# OPA4377__V1_0.net
KiCad netlist of a schematic drawn in EasyEDA Pro
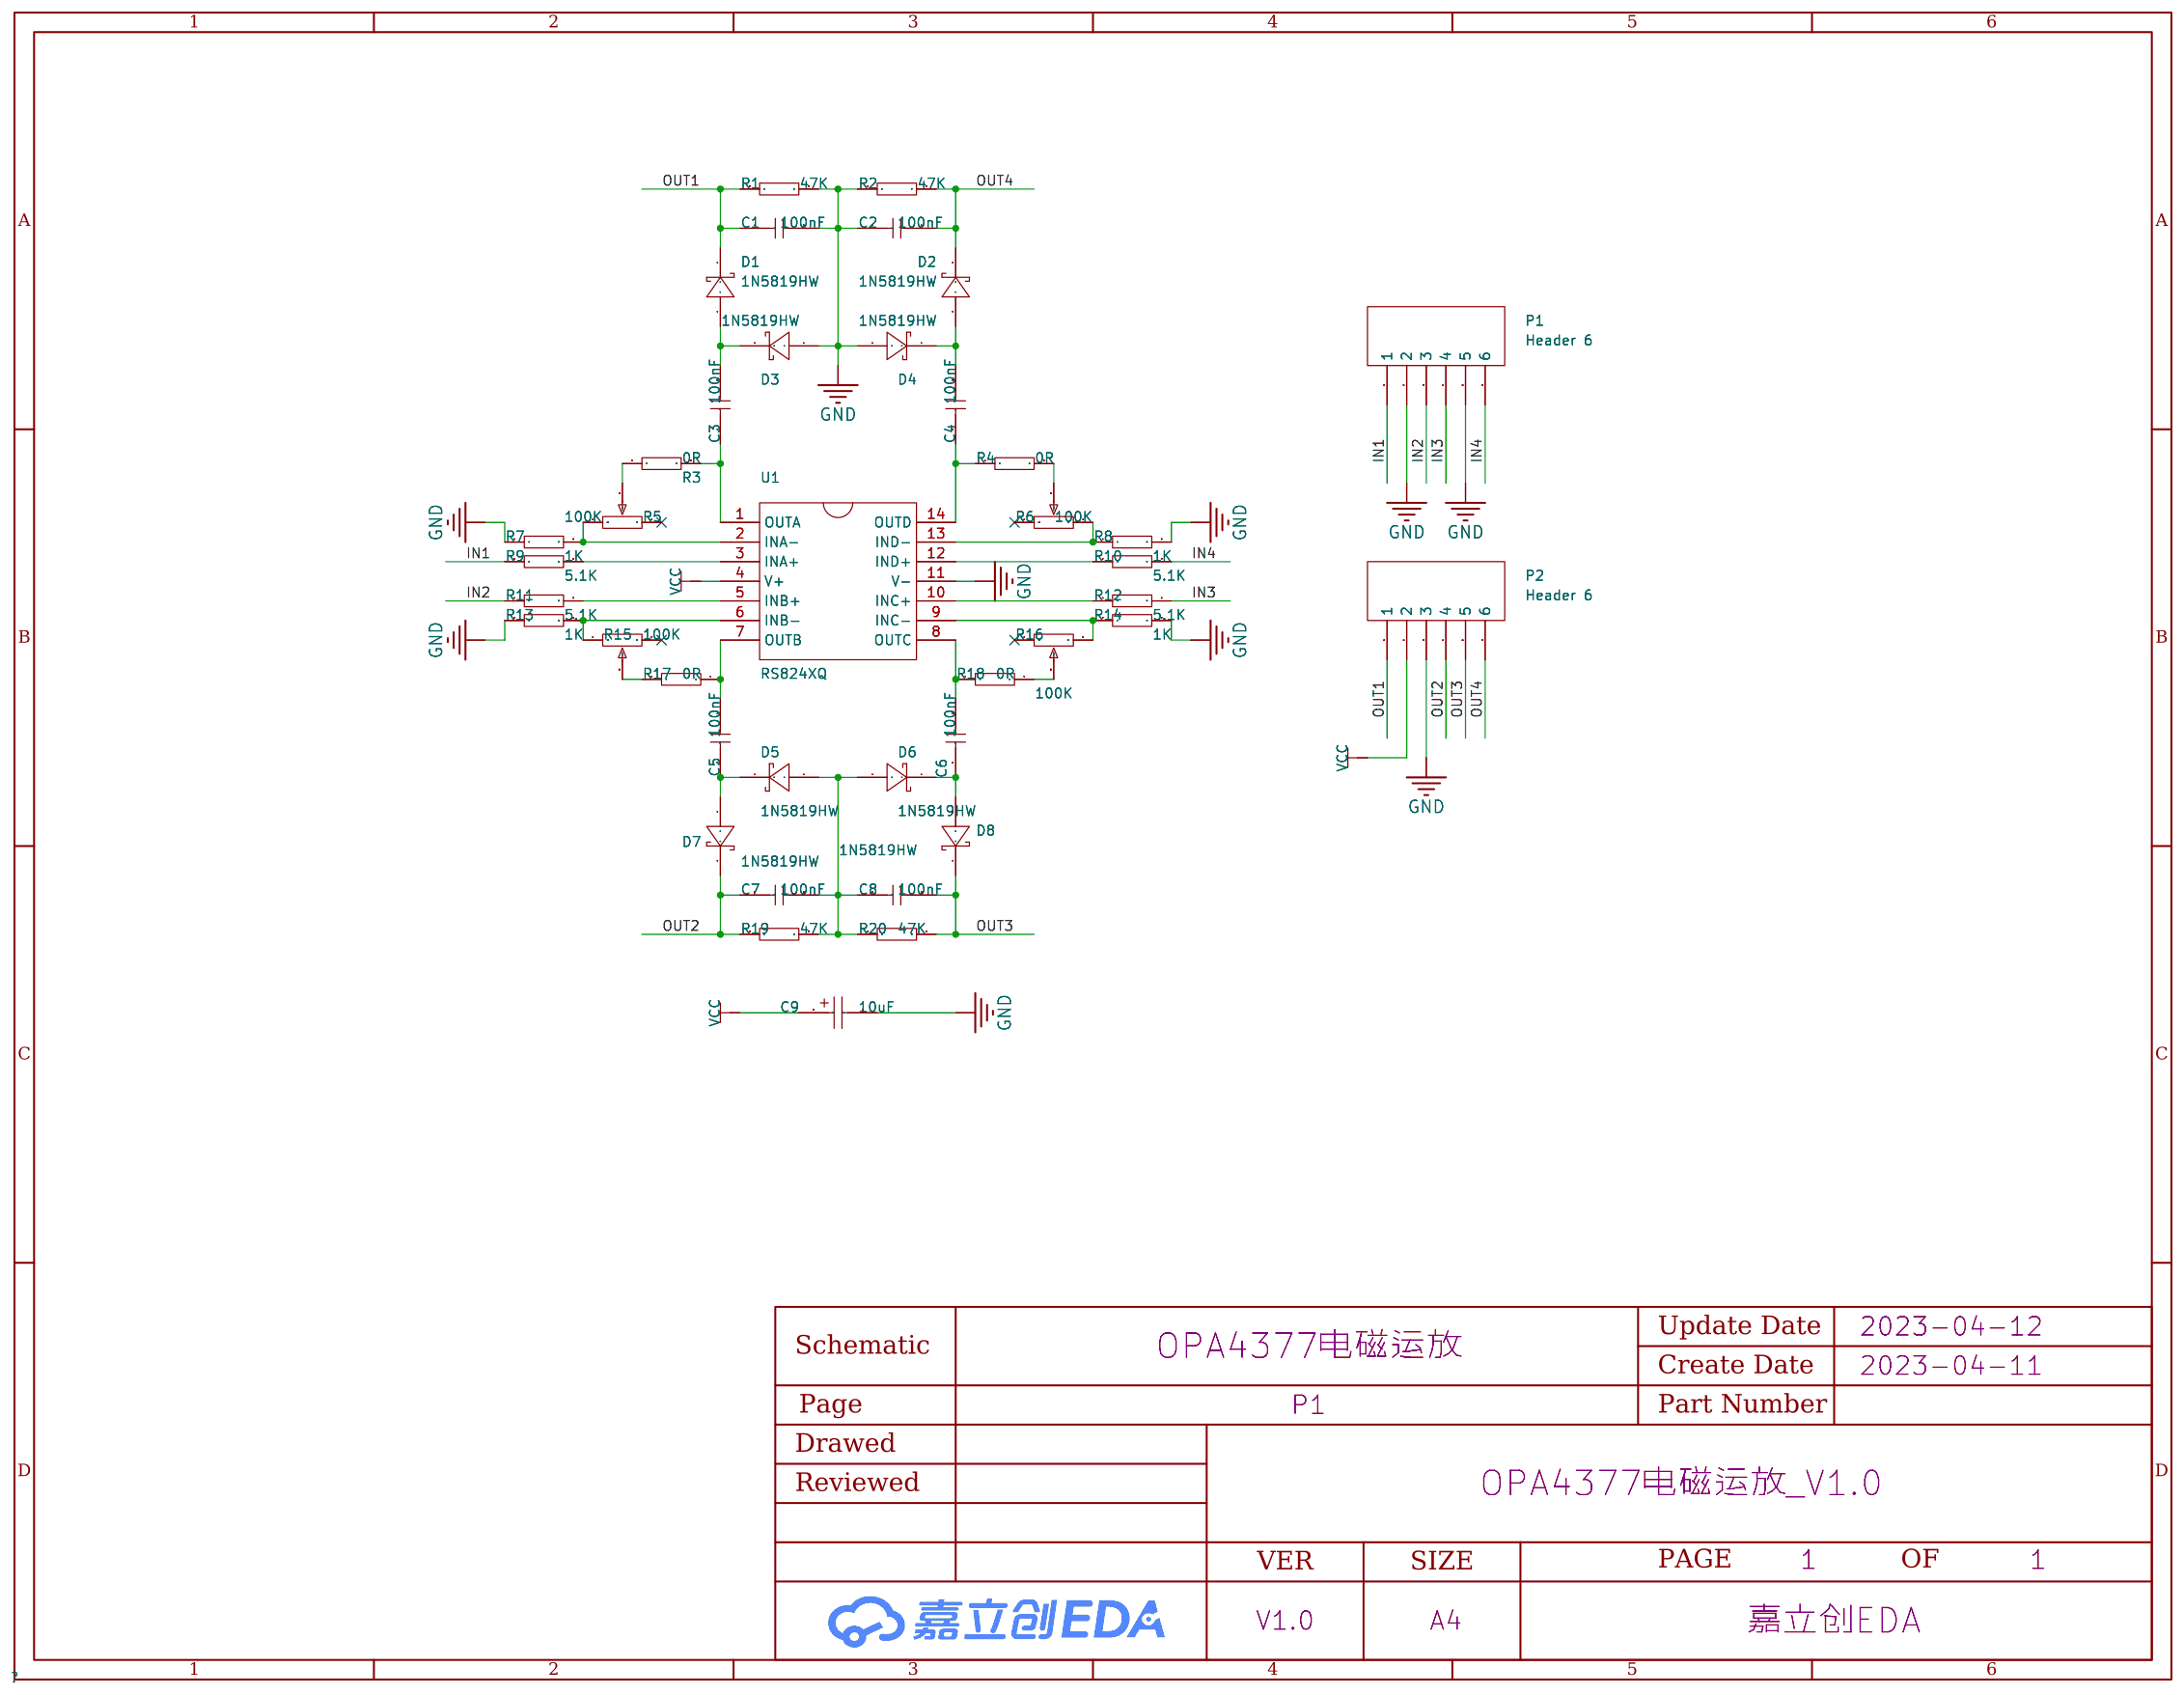
[diagram p0: schematic sheet]

(export (version "E")
  (design (tool "Eeschema 10.0.6"))
  (components
    (comp (ref "C1")
      (value "100nF")
      (footprint "easyedapro:CAPC1608[0603]S-L")
      (libsource (lib "easyedapro") (part "100nF 0603 50V X7R"))
    )
    (comp (ref "C2")
      (value "100nF")
      (footprint "easyedapro:CAPC1608[0603]S-L")
      (libsource (lib "easyedapro") (part "100nF 0603 50V X7R"))
    )
    (comp (ref "C3")
      (value "100nF")
      (footprint "easyedapro:CAPC1608[0603]S-L")
      (libsource (lib "easyedapro") (part "100nF 0603 50V X7R"))
    )
    (comp (ref "C4")
      (value "100nF")
      (footprint "easyedapro:CAPC1608[0603]S-L")
      (libsource (lib "easyedapro") (part "100nF 0603 50V X7R"))
    )
    (comp (ref "C5")
      (value "100nF")
      (footprint "easyedapro:CAPC1608[0603]S-L")
      (libsource (lib "easyedapro") (part "100nF 0603 50V X7R"))
    )
    (comp (ref "C6")
      (value "100nF")
      (footprint "easyedapro:CAPC1608[0603]S-L")
      (libsource (lib "easyedapro") (part "100nF 0603 50V X7R"))
    )
    (comp (ref "C7")
      (value "100nF")
      (footprint "easyedapro:CAPC1608[0603]S-L")
      (libsource (lib "easyedapro") (part "100nF 0603 50V X7R"))
    )
    (comp (ref "C8")
      (value "100nF")
      (footprint "easyedapro:CAPC1608[0603]S-L")
      (libsource (lib "easyedapro") (part "100nF 0603 50V X7R"))
    )
    (comp (ref "C9")
      (value "10uF")
      (footprint "easyedapro:CAPT3216")
      (libsource (lib "easyedapro") (part "10uF 3216 16V"))
    )
    (comp (ref "D1")
      (value "1N5819HW")
      (footprint "easyedapro:SOD-123-L")
      (libsource (lib "easyedapro") (part "1N5819HW"))
    )
    (comp (ref "D2")
      (value "1N5819HW")
      (footprint "easyedapro:SOD-123-L")
      (libsource (lib "easyedapro") (part "1N5819HW"))
    )
    (comp (ref "D3")
      (value "1N5819HW")
      (footprint "easyedapro:SOD-123-L")
      (libsource (lib "easyedapro") (part "1N5819HW"))
    )
    (comp (ref "D4")
      (value "1N5819HW")
      (footprint "easyedapro:SOD-123-L")
      (libsource (lib "easyedapro") (part "1N5819HW"))
    )
    (comp (ref "D5")
      (value "1N5819HW")
      (footprint "easyedapro:SOD-123-L")
      (libsource (lib "easyedapro") (part "1N5819HW"))
    )
    (comp (ref "D6")
      (value "1N5819HW")
      (footprint "easyedapro:SOD-123-L")
      (libsource (lib "easyedapro") (part "1N5819HW"))
    )
    (comp (ref "D7")
      (value "1N5819HW")
      (footprint "easyedapro:SOD-123-L")
      (libsource (lib "easyedapro") (part "1N5819HW"))
    )
    (comp (ref "D8")
      (value "1N5819HW")
      (footprint "easyedapro:SOD-123-L")
      (libsource (lib "easyedapro") (part "1N5819HW"))
    )
    (comp (ref "P1")
      (value "Header 6")
      (footprint "easyedapro:HDR1X6")
      (libsource (lib "easyedapro") (part "Header 6"))
    )
    (comp (ref "P2")
      (value "Header 6")
      (footprint "easyedapro:HDR1X6")
      (libsource (lib "easyedapro") (part "Header 6"))
    )
    (comp (ref "R1")
      (value "47K")
      (footprint "easyedapro:RESC1608[0603]S-L")
      (libsource (lib "easyedapro") (part "Res-Chip_3"))
    )
    (comp (ref "R2")
      (value "47K")
      (footprint "easyedapro:RESC1608[0603]S-L")
      (libsource (lib "easyedapro") (part "Res-Chip_3"))
    )
    (comp (ref "R3")
      (value "0R")
      (footprint "easyedapro:RESC1608[0603]S-L")
      (libsource (lib "easyedapro") (part "Res-Chip"))
    )
    (comp (ref "R4")
      (value "0R")
      (footprint "easyedapro:RESC1608[0603]S-L")
      (libsource (lib "easyedapro") (part "Res-Chip"))
    )
    (comp (ref "R5")
      (value "100K")
      (footprint "easyedapro:RESPOT3296W")
      (libsource (lib "easyedapro") (part "Res-Adj-3p"))
    )
    (comp (ref "R6")
      (value "100K")
      (footprint "easyedapro:RESPOT3296W")
      (libsource (lib "easyedapro") (part "Res-Adj-3p"))
    )
    (comp (ref "R7")
      (value "1K")
      (footprint "easyedapro:RESC1608[0603]S-L")
      (libsource (lib "easyedapro") (part "Res-Chip_1"))
    )
    (comp (ref "R8")
      (value "1K")
      (footprint "easyedapro:RESC1608[0603]S-L")
      (libsource (lib "easyedapro") (part "Res-Chip_1"))
    )
    (comp (ref "R9")
      (value "5.1K")
      (footprint "easyedapro:RESC1608[0603]S-L")
      (libsource (lib "easyedapro") (part "Res-Chip_2"))
    )
    (comp (ref "R10")
      (value "5.1K")
      (footprint "easyedapro:RESC1608[0603]S-L")
      (libsource (lib "easyedapro") (part "Res-Chip_2"))
    )
    (comp (ref "R11")
      (value "5.1K")
      (footprint "easyedapro:RESC1608[0603]S-L")
      (libsource (lib "easyedapro") (part "Res-Chip_2"))
    )
    (comp (ref "R12")
      (value "5.1K")
      (footprint "easyedapro:RESC1608[0603]S-L")
      (libsource (lib "easyedapro") (part "Res-Chip_2"))
    )
    (comp (ref "R13")
      (value "1K")
      (footprint "easyedapro:RESC1608[0603]S-L")
      (libsource (lib "easyedapro") (part "Res-Chip_1"))
    )
    (comp (ref "R14")
      (value "1K")
      (footprint "easyedapro:RESC1608[0603]S-L")
      (libsource (lib "easyedapro") (part "Res-Chip_1"))
    )
    (comp (ref "R15")
      (value "100K")
      (footprint "easyedapro:RESPOT3296W")
      (libsource (lib "easyedapro") (part "Res-Adj-3p"))
    )
    (comp (ref "R16")
      (value "100K")
      (footprint "easyedapro:RESPOT3296W")
      (libsource (lib "easyedapro") (part "Res-Adj-3p"))
    )
    (comp (ref "R17")
      (value "0R")
      (footprint "easyedapro:RESC1608[0603]S-L")
      (libsource (lib "easyedapro") (part "Res-Chip"))
    )
    (comp (ref "R18")
      (value "0R")
      (footprint "easyedapro:RESC1608[0603]S-L")
      (libsource (lib "easyedapro") (part "Res-Chip"))
    )
    (comp (ref "R19")
      (value "47K")
      (footprint "easyedapro:RESC1608[0603]S-L")
      (libsource (lib "easyedapro") (part "Res-Chip_3"))
    )
    (comp (ref "R20")
      (value "47K")
      (footprint "easyedapro:RESC1608[0603]S-L")
      (libsource (lib "easyedapro") (part "Res-Chip_3"))
    )
    (comp (ref "U1")
      (value "RS824XQ")
      (footprint "easyedapro:TSSOP-14")
      (libsource (lib "easyedapro") (part "RS824XQ"))
    )
  )
  (nets
    (net (code "1") (name "/IN1") (class "Default")
      (node (ref "P1") (pin "1") (pinfunction "1_1") (pintype "input"))
      (node (ref "R9") (pin "1") (pinfunction "1_1") (pintype "input"))
    )
    (net (code "2") (name "/IN2") (class "Default")
      (node (ref "P1") (pin "3") (pinfunction "3_3") (pintype "input"))
      (node (ref "R11") (pin "1") (pinfunction "1_1") (pintype "input"))
    )
    (net (code "3") (name "/IN3") (class "Default")
      (node (ref "P1") (pin "4") (pinfunction "4_4") (pintype "input"))
      (node (ref "R12") (pin "2") (pinfunction "2_2") (pintype "input"))
    )
    (net (code "4") (name "/IN4") (class "Default")
      (node (ref "P1") (pin "6") (pinfunction "6_6") (pintype "input"))
      (node (ref "R10") (pin "2") (pinfunction "2_2") (pintype "input"))
    )
    (net (code "5") (name "/OUT1") (class "Default")
      (node (ref "C1") (pin "1") (pinfunction "1_1") (pintype "input"))
      (node (ref "D1") (pin "K") (pinfunction "K_K") (pintype "input"))
      (node (ref "P2") (pin "1") (pinfunction "1_1") (pintype "input"))
      (node (ref "R1") (pin "1") (pinfunction "1_1") (pintype "input"))
    )
    (net (code "6") (name "/OUT2") (class "Default")
      (node (ref "C7") (pin "1") (pinfunction "1_1") (pintype "input"))
      (node (ref "D7") (pin "K") (pinfunction "K_K") (pintype "input"))
      (node (ref "P2") (pin "4") (pinfunction "4_4") (pintype "input"))
      (node (ref "R19") (pin "1") (pinfunction "1_1") (pintype "input"))
    )
    (net (code "7") (name "/OUT3") (class "Default")
      (node (ref "C8") (pin "2") (pinfunction "2_2") (pintype "input"))
      (node (ref "D8") (pin "K") (pinfunction "K_K") (pintype "input"))
      (node (ref "P2") (pin "5") (pinfunction "5_5") (pintype "input"))
      (node (ref "R20") (pin "2") (pinfunction "2_2") (pintype "input"))
    )
    (net (code "8") (name "/OUT4") (class "Default")
      (node (ref "C2") (pin "2") (pinfunction "2_2") (pintype "input"))
      (node (ref "D2") (pin "K") (pinfunction "K_K") (pintype "input"))
      (node (ref "P2") (pin "6") (pinfunction "6_6") (pintype "input"))
      (node (ref "R2") (pin "2") (pinfunction "2_2") (pintype "input"))
    )
    (net (code "9") (name "GND") (class "Default")
      (node (ref "C1") (pin "2") (pinfunction "2_2") (pintype "input"))
      (node (ref "C2") (pin "1") (pinfunction "1_1") (pintype "input"))
      (node (ref "C9") (pin "2") (pinfunction "2_2") (pintype "input"))
      (node (ref "D3") (pin "A") (pinfunction "A_A") (pintype "input"))
      (node (ref "D4") (pin "A") (pinfunction "A_A") (pintype "input"))
      (node (ref "P1") (pin "2") (pinfunction "2_2") (pintype "input"))
      (node (ref "P1") (pin "5") (pinfunction "5_5") (pintype "input"))
      (node (ref "P2") (pin "3") (pinfunction "3_3") (pintype "input"))
      (node (ref "R1") (pin "2") (pinfunction "2_2") (pintype "input"))
      (node (ref "R13") (pin "1") (pinfunction "1_1") (pintype "input"))
      (node (ref "R14") (pin "2") (pinfunction "2_2") (pintype "input"))
      (node (ref "R2") (pin "1") (pinfunction "1_1") (pintype "input"))
      (node (ref "R7") (pin "1") (pinfunction "1_1") (pintype "input"))
      (node (ref "R8") (pin "2") (pinfunction "2_2") (pintype "input"))
      (node (ref "U1") (pin "11") (pinfunction "V-_11") (pintype "input"))
    )
    (net (code "10") (name "Net-(C3-Pad2)") (class "Default")
      (node (ref "C3") (pin "2") (pinfunction "2_2") (pintype "input"))
      (node (ref "D1") (pin "A") (pinfunction "A_A") (pintype "input"))
      (node (ref "D3") (pin "K") (pinfunction "K_K") (pintype "input"))
    )
    (net (code "11") (name "Net-(C4-Pad2)") (class "Default")
      (node (ref "C4") (pin "2") (pinfunction "2_2") (pintype "input"))
      (node (ref "D2") (pin "A") (pinfunction "A_A") (pintype "input"))
      (node (ref "D4") (pin "K") (pinfunction "K_K") (pintype "input"))
    )
    (net (code "12") (name "Net-(C5-Pad2)") (class "Default")
      (node (ref "C5") (pin "2") (pinfunction "2_2") (pintype "input"))
      (node (ref "D5") (pin "K") (pinfunction "K_K") (pintype "input"))
      (node (ref "D7") (pin "A") (pinfunction "A_A") (pintype "input"))
    )
    (net (code "13") (name "Net-(C6-Pad1)") (class "Default")
      (node (ref "C6") (pin "1") (pinfunction "1_1") (pintype "input"))
      (node (ref "D6") (pin "K") (pinfunction "K_K") (pintype "input"))
      (node (ref "D8") (pin "A") (pinfunction "A_A") (pintype "input"))
    )
    (net (code "14") (name "Net-(C7-Pad2)") (class "Default")
      (node (ref "C7") (pin "2") (pinfunction "2_2") (pintype "input"))
      (node (ref "C8") (pin "1") (pinfunction "1_1") (pintype "input"))
      (node (ref "D5") (pin "A") (pinfunction "A_A") (pintype "input"))
      (node (ref "D6") (pin "A") (pinfunction "A_A") (pintype "input"))
      (node (ref "R19") (pin "2") (pinfunction "2_2") (pintype "input"))
      (node (ref "R20") (pin "1") (pinfunction "1_1") (pintype "input"))
    )
    (net (code "15") (name "Net-(R3-Pad1)") (class "Default")
      (node (ref "R3") (pin "1") (pinfunction "1_1") (pintype "input"))
      (node (ref "R5") (pin "ADJ") (pinfunction "ADJ_ADJ") (pintype "input"))
    )
    (net (code "16") (name "Net-(R4-Pad2)") (class "Default")
      (node (ref "R4") (pin "2") (pinfunction "2_2") (pintype "input"))
      (node (ref "R6") (pin "ADJ") (pinfunction "ADJ_ADJ") (pintype "input"))
    )
    (net (code "17") (name "Net-(R5-BOT)") (class "Default")
      (node (ref "R5") (pin "2") (pinfunction "BOT_2") (pintype "input"))
      (node (ref "R7") (pin "2") (pinfunction "2_2") (pintype "input"))
      (node (ref "U1") (pin "2") (pinfunction "INA-_2") (pintype "input"))
    )
    (net (code "18") (name "Net-(R6-TOP)") (class "Default")
      (node (ref "R6") (pin "1") (pinfunction "TOP_1") (pintype "input"))
      (node (ref "R8") (pin "1") (pinfunction "1_1") (pintype "input"))
      (node (ref "U1") (pin "13") (pinfunction "IND-_13") (pintype "input"))
    )
    (net (code "19") (name "Net-(R15-PadADJ)") (class "Default")
      (node (ref "R15") (pin "ADJ") (pinfunction "ADJ_ADJ") (pintype "input"))
      (node (ref "R17") (pin "1") (pinfunction "1_1") (pintype "input"))
    )
    (net (code "20") (name "Net-(R15-TOP)") (class "Default")
      (node (ref "R13") (pin "2") (pinfunction "2_2") (pintype "input"))
      (node (ref "R15") (pin "1") (pinfunction "TOP_1") (pintype "input"))
      (node (ref "U1") (pin "6") (pinfunction "INB-_6") (pintype "input"))
    )
    (net (code "21") (name "Net-(R16-BOT)") (class "Default")
      (node (ref "R14") (pin "1") (pinfunction "1_1") (pintype "input"))
      (node (ref "R16") (pin "2") (pinfunction "BOT_2") (pintype "input"))
      (node (ref "U1") (pin "9") (pinfunction "INC-_9") (pintype "input"))
    )
    (net (code "22") (name "Net-(R16-PadADJ)") (class "Default")
      (node (ref "R16") (pin "ADJ") (pinfunction "ADJ_ADJ") (pintype "input"))
      (node (ref "R18") (pin "2") (pinfunction "2_2") (pintype "input"))
    )
    (net (code "23") (name "Net-(U1-INA+)") (class "Default")
      (node (ref "R9") (pin "2") (pinfunction "2_2") (pintype "input"))
      (node (ref "U1") (pin "3") (pinfunction "INA+_3") (pintype "input"))
    )
    (net (code "24") (name "Net-(U1-INB+)") (class "Default")
      (node (ref "R11") (pin "2") (pinfunction "2_2") (pintype "input"))
      (node (ref "U1") (pin "5") (pinfunction "INB+_5") (pintype "input"))
    )
    (net (code "25") (name "Net-(U1-INC+)") (class "Default")
      (node (ref "R12") (pin "1") (pinfunction "1_1") (pintype "input"))
      (node (ref "U1") (pin "10") (pinfunction "INC+_10") (pintype "input"))
    )
    (net (code "26") (name "Net-(U1-IND+)") (class "Default")
      (node (ref "R10") (pin "1") (pinfunction "1_1") (pintype "input"))
      (node (ref "U1") (pin "12") (pinfunction "IND+_12") (pintype "input"))
    )
    (net (code "27") (name "Net-(U1-OUTA)") (class "Default")
      (node (ref "C3") (pin "1") (pinfunction "1_1") (pintype "input"))
      (node (ref "R3") (pin "2") (pinfunction "2_2") (pintype "input"))
      (node (ref "U1") (pin "1") (pinfunction "OUTA_1") (pintype "input"))
    )
    (net (code "28") (name "Net-(U1-OUTB)") (class "Default")
      (node (ref "C5") (pin "1") (pinfunction "1_1") (pintype "input"))
      (node (ref "R17") (pin "2") (pinfunction "2_2") (pintype "input"))
      (node (ref "U1") (pin "7") (pinfunction "OUTB_7") (pintype "input"))
    )
    (net (code "29") (name "Net-(U1-OUTC)") (class "Default")
      (node (ref "C6") (pin "2") (pinfunction "2_2") (pintype "input"))
      (node (ref "R18") (pin "1") (pinfunction "1_1") (pintype "input"))
      (node (ref "U1") (pin "8") (pinfunction "OUTC_8") (pintype "input"))
    )
    (net (code "30") (name "Net-(U1-OUTD)") (class "Default")
      (node (ref "C4") (pin "1") (pinfunction "1_1") (pintype "input"))
      (node (ref "R4") (pin "1") (pinfunction "1_1") (pintype "input"))
      (node (ref "U1") (pin "14") (pinfunction "OUTD_14") (pintype "input"))
    )
    (net (code "31") (name "VCC") (class "Default")
      (node (ref "C9") (pin "1") (pinfunction "1_1") (pintype "input"))
      (node (ref "P2") (pin "2") (pinfunction "2_2") (pintype "input"))
      (node (ref "U1") (pin "4") (pinfunction "V+_4") (pintype "input"))
    )
    (net (code "32") (name "unconnected-(R5-TOP-Pad1)") (class "Default")
      (node (ref "R5") (pin "1") (pinfunction "TOP_1") (pintype "input+no_connect"))
    )
    (net (code "33") (name "unconnected-(R6-BOT-Pad2)") (class "Default")
      (node (ref "R6") (pin "2") (pinfunction "BOT_2") (pintype "input+no_connect"))
    )
    (net (code "34") (name "unconnected-(R15-BOT-Pad2)") (class "Default")
      (node (ref "R15") (pin "2") (pinfunction "BOT_2") (pintype "input+no_connect"))
    )
    (net (code "35") (name "unconnected-(R16-TOP-Pad1)") (class "Default")
      (node (ref "R16") (pin "1") (pinfunction "TOP_1") (pintype "input+no_connect"))
    )
  )
)
